# SafetySwitch.net
KiCad netlist of a schematic drawn in Altium Designer
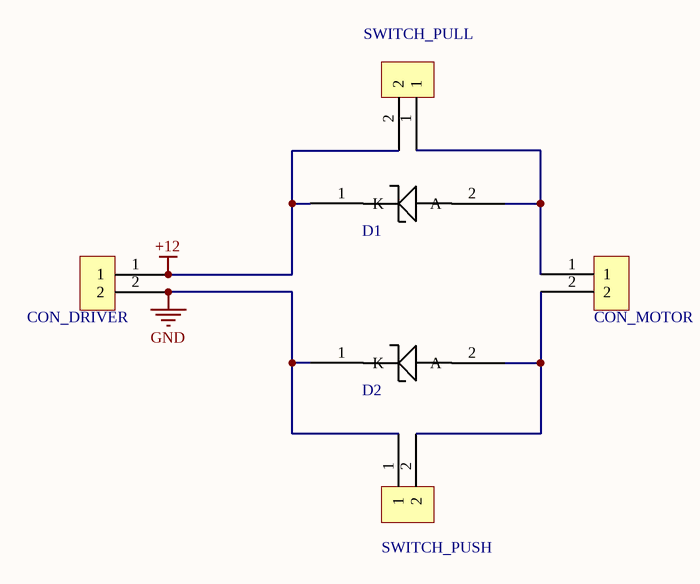
[diagram p0: SafetySwitch.SchDoc]

(export (version "E")
  (design (tool "Eeschema 10.0.6"))
  (components
    (comp (ref "CON_DRIVER")
      (value "KF301-5.0-2P")
      (footprint "KF301-5.0-2P")
      (libsource (lib "") (part "KF301-5.0-2P_1"))
    )
    (comp (ref "CON_MOTOR")
      (value "KF301-5.0-2P")
      (footprint "KF301-5.0-2P")
      (libsource (lib "KF301-5.0-2P") (part "KF301-5.0-2P"))
    )
    (comp (ref "D1") (value "CMS04") (libsource (lib "CMS04") (part "CMS04")))
    (comp (ref "D2") (value "CMS04") (libsource (lib "CMS04") (part "CMS04")))
    (comp (ref "SWITCH_PULL")
      (value "KF301-5.0-2P")
      (footprint "KF301-5.0-2P")
      (libsource (lib "KF301-5.0-2P") (part "KF301-5.0-2P"))
    )
    (comp (ref "SWITCH_PUSH")
      (value "KF301-5.0-2P")
      (footprint "KF301-5.0-2P")
      (libsource (lib "") (part "KF301-5.0-2P_2"))
    )
  )
  (nets
    (net (code "1") (name "+12") (class "Default")
      (node (ref "CON_DRIVER") (pin "1") (pinfunction "1_1") (pintype "passive"))
      (node (ref "D1") (pin "1") (pinfunction "K_1") (pintype "passive"))
      (node (ref "SWITCH_PULL") (pin "2") (pinfunction "2_2") (pintype "passive"))
    )
    (net (code "2") (name "GND") (class "Default")
      (node (ref "CON_DRIVER") (pin "2") (pinfunction "2_2") (pintype "passive"))
      (node (ref "D2") (pin "1") (pinfunction "K_1") (pintype "passive"))
      (node (ref "SWITCH_PUSH") (pin "1") (pinfunction "1_1") (pintype "passive"))
    )
    (net (code "3") (name "Net-(D1-A)") (class "Default")
      (node (ref "CON_MOTOR") (pin "1") (pinfunction "1_1") (pintype "passive"))
      (node (ref "D1") (pin "2") (pinfunction "A_2") (pintype "passive"))
      (node (ref "SWITCH_PULL") (pin "1") (pinfunction "1_1") (pintype "passive"))
    )
    (net (code "4") (name "Net-(D2-A)") (class "Default")
      (node (ref "CON_MOTOR") (pin "2") (pinfunction "2_2") (pintype "passive"))
      (node (ref "D2") (pin "2") (pinfunction "A_2") (pintype "passive"))
      (node (ref "SWITCH_PUSH") (pin "2") (pinfunction "2_2") (pintype "passive"))
    )
  )
)
